# POWER.net
KiCad netlist of a schematic drawn in Altium Designer
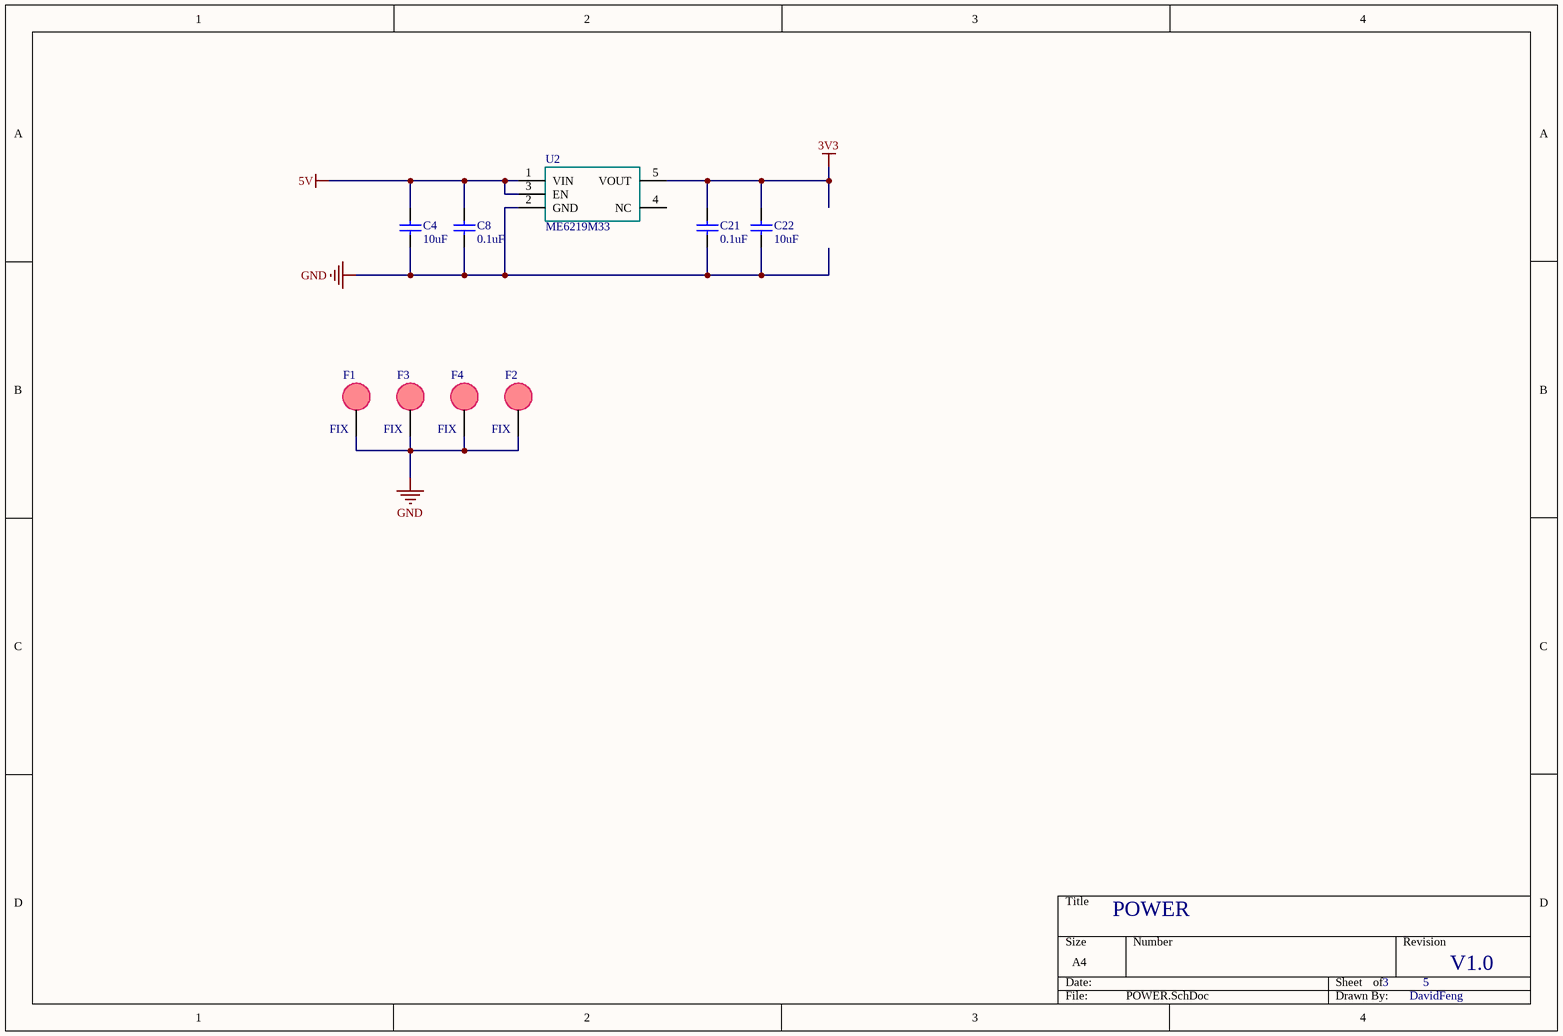
[diagram p0: POWER.SchDoc]

(export (version "E")
  (design (tool "Eeschema 10.0.6"))
  (components
    (comp (ref "C4")
      (value "10uF")
      (footprint "C0805")
      (description "Capacitor")
      (fields (field (name "PUBLISHER") "Altium Limited"))
      (libsource (lib "Miscellaneous Devices") (part "Cap"))
    )
    (comp (ref "C8")
      (value "0.1uF")
      (footprint "C0603")
      (description "Capacitor")
      (fields (field (name "PUBLISHER") "Altium Limited"))
      (libsource (lib "Miscellaneous Devices") (part "Cap"))
    )
    (comp (ref "C21")
      (value "0.1uF")
      (footprint "C0603")
      (description "Capacitor")
      (fields (field (name "PUBLISHER") "Altium Limited"))
      (libsource (lib "Miscellaneous Devices") (part "Cap"))
    )
    (comp (ref "C22")
      (value "10uF")
      (footprint "C0805")
      (description "Capacitor")
      (fields (field (name "PUBLISHER") "Altium Limited"))
      (libsource (lib "Miscellaneous Devices") (part "Cap"))
    )
    (comp (ref "F1") (value "FIX") (footprint "FIX-2.0") (libsource (lib "Genius_Schlib") (part "FIX")))
    (comp (ref "F2") (value "FIX") (footprint "FIX-2.0") (libsource (lib "Genius_Schlib") (part "FIX")))
    (comp (ref "F3") (value "FIX") (footprint "FIX-2.0") (libsource (lib "Genius_Schlib") (part "FIX")))
    (comp (ref "F4") (value "FIX") (footprint "FIX-2.0") (libsource (lib "Genius_Schlib") (part "FIX")))
    (comp (ref "U2")
      (value "ME6219M33")
      (footprint "SOT23-5")
      (description "LOW-POWER 100-mA LOW-DROPOUT LINEAR REGULATORS")
      (libsource (lib "Genius_Schlib") (part "ME6219"))
    )
  )
  (nets
    (net (code "1") (name "3V3") (class "Default")
      (node (ref "C21") (pin "2") (pinfunction "2_2") (pintype "passive"))
      (node (ref "C22") (pin "2") (pinfunction "2_2") (pintype "passive"))
      (node (ref "U2") (pin "5") (pinfunction "VOUT_5") (pintype "passive"))
    )
    (net (code "2") (name "5V") (class "Default")
      (node (ref "C4") (pin "2") (pinfunction "2_2") (pintype "passive"))
      (node (ref "C8") (pin "2") (pinfunction "2_2") (pintype "passive"))
      (node (ref "U2") (pin "1") (pinfunction "VIN_1") (pintype "passive"))
      (node (ref "U2") (pin "3") (pinfunction "EN_3") (pintype "passive"))
    )
    (net (code "3") (name "GND") (class "Default")
      (node (ref "C21") (pin "1") (pinfunction "1_1") (pintype "passive"))
      (node (ref "C22") (pin "1") (pinfunction "1_1") (pintype "passive"))
      (node (ref "C4") (pin "1") (pinfunction "1_1") (pintype "passive"))
      (node (ref "C8") (pin "1") (pinfunction "1_1") (pintype "passive"))
      (node (ref "F1") (pin "0") (pinfunction "0_0") (pintype "passive"))
      (node (ref "F2") (pin "0") (pinfunction "0_0") (pintype "passive"))
      (node (ref "F3") (pin "0") (pinfunction "0_0") (pintype "passive"))
      (node (ref "F4") (pin "0") (pinfunction "0_0") (pintype "passive"))
      (node (ref "U2") (pin "2") (pinfunction "GND_2") (pintype "passive"))
    )
    (net (code "4") (name "unconnected-(U2-NC-Pad4)") (class "Default")
      (node (ref "U2") (pin "4") (pinfunction "NC_4") (pintype "passive"))
    )
  )
)
